# 35-CSI-GPM-CDSS_INTERFACE.net
KiCad netlist of a schematic drawn in Altium Designer
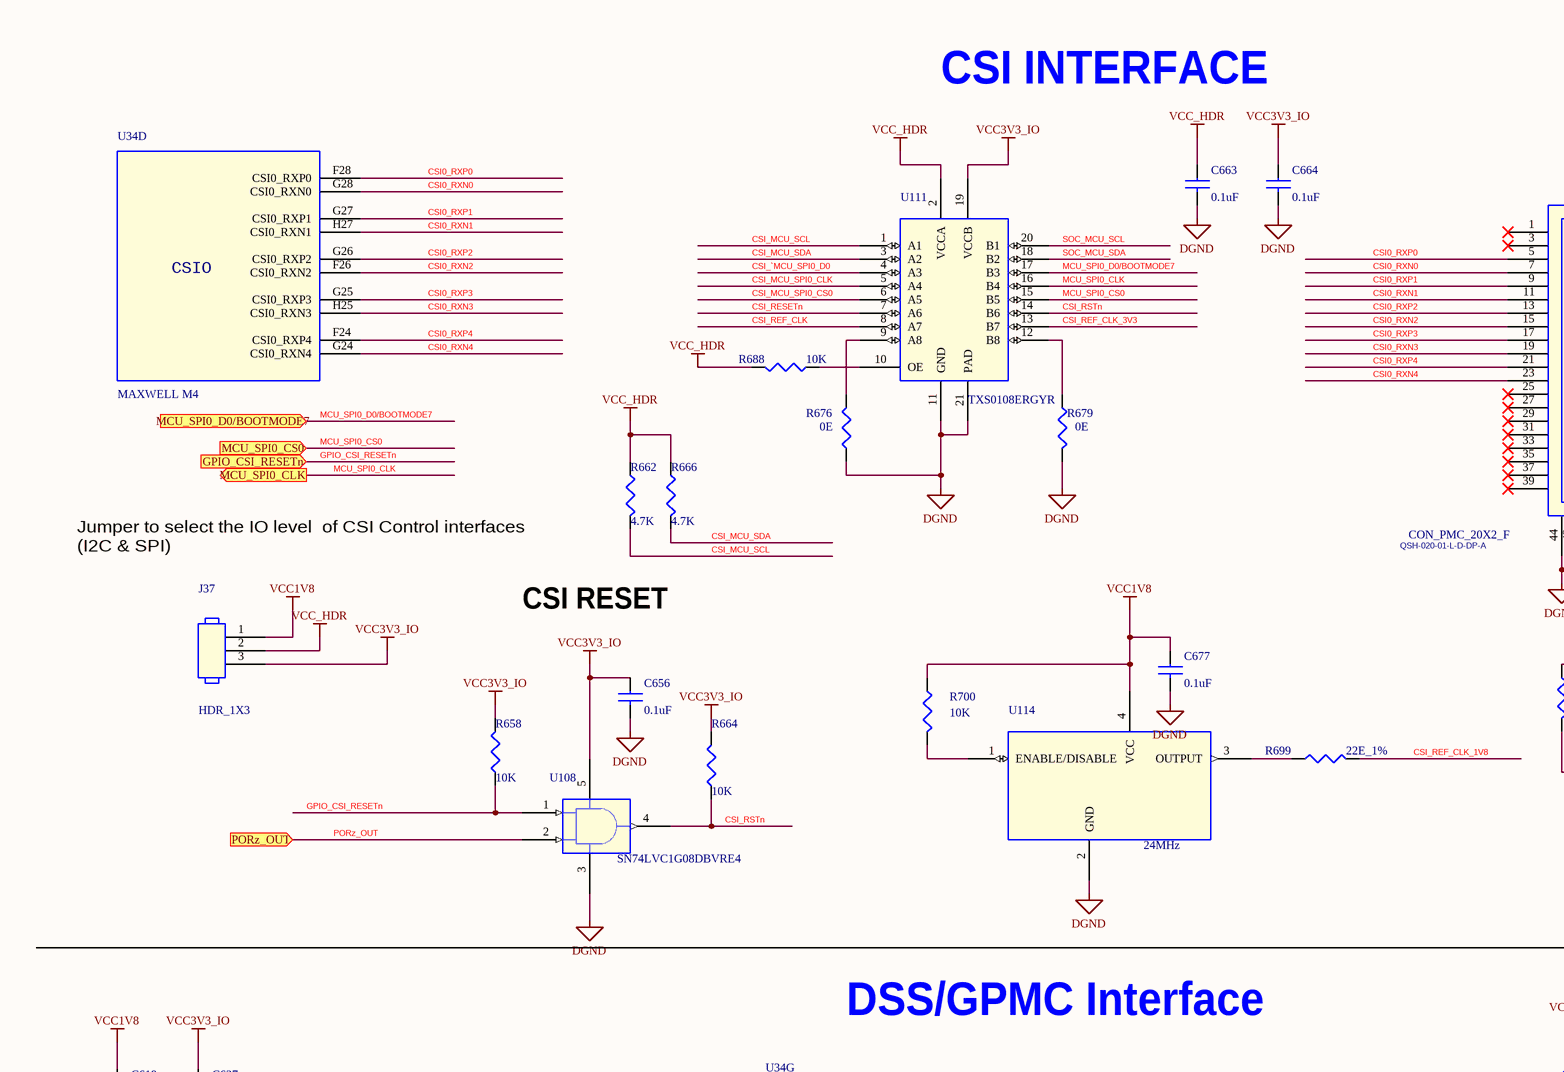
[diagram p0: 35-CSI-GPM-CDSS INTERFACE.SchDoc, top left]
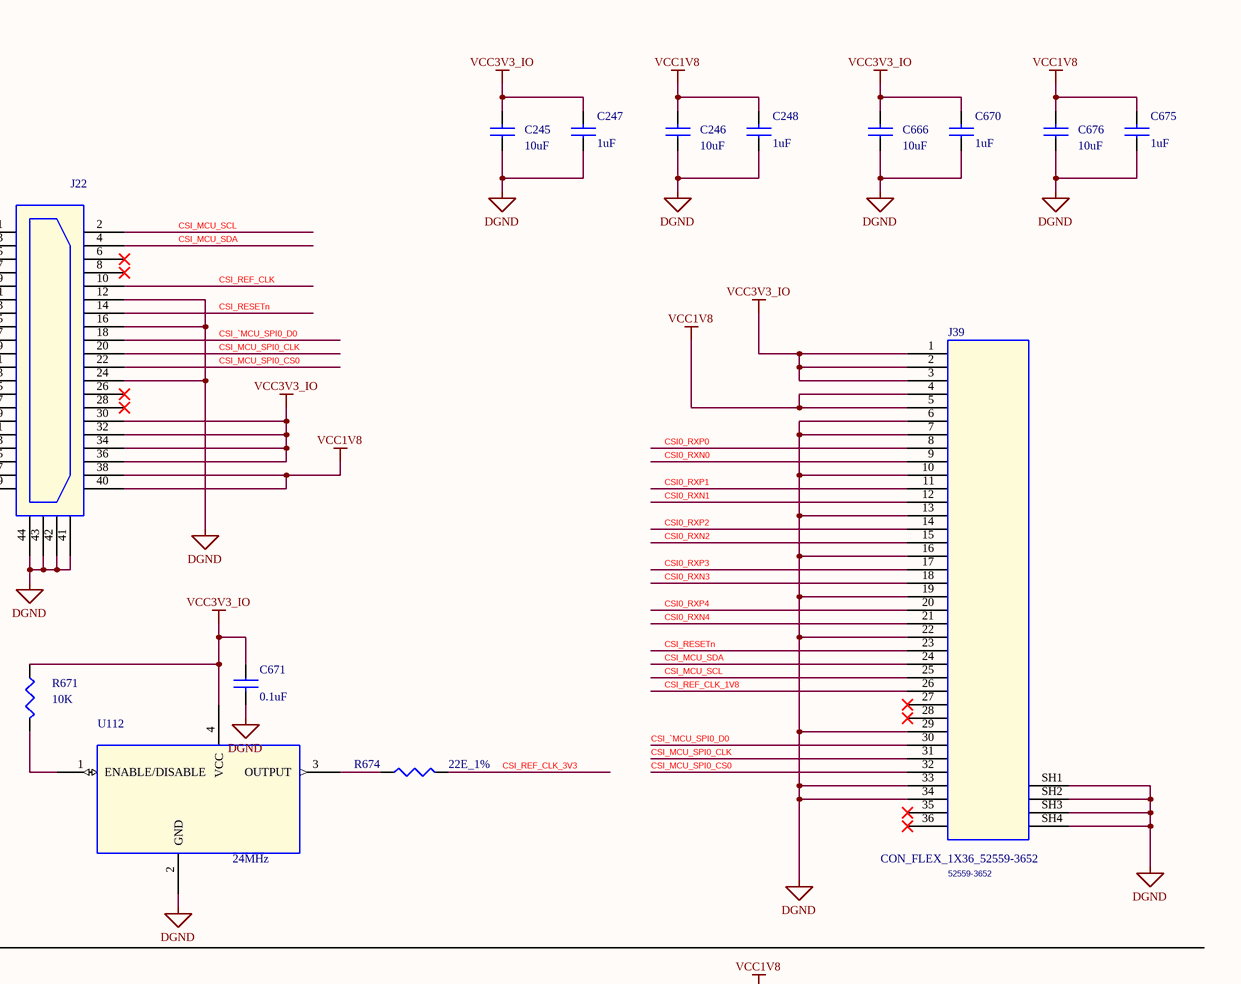
[diagram p1: 35-CSI-GPM-CDSS INTERFACE.SchDoc, top right]
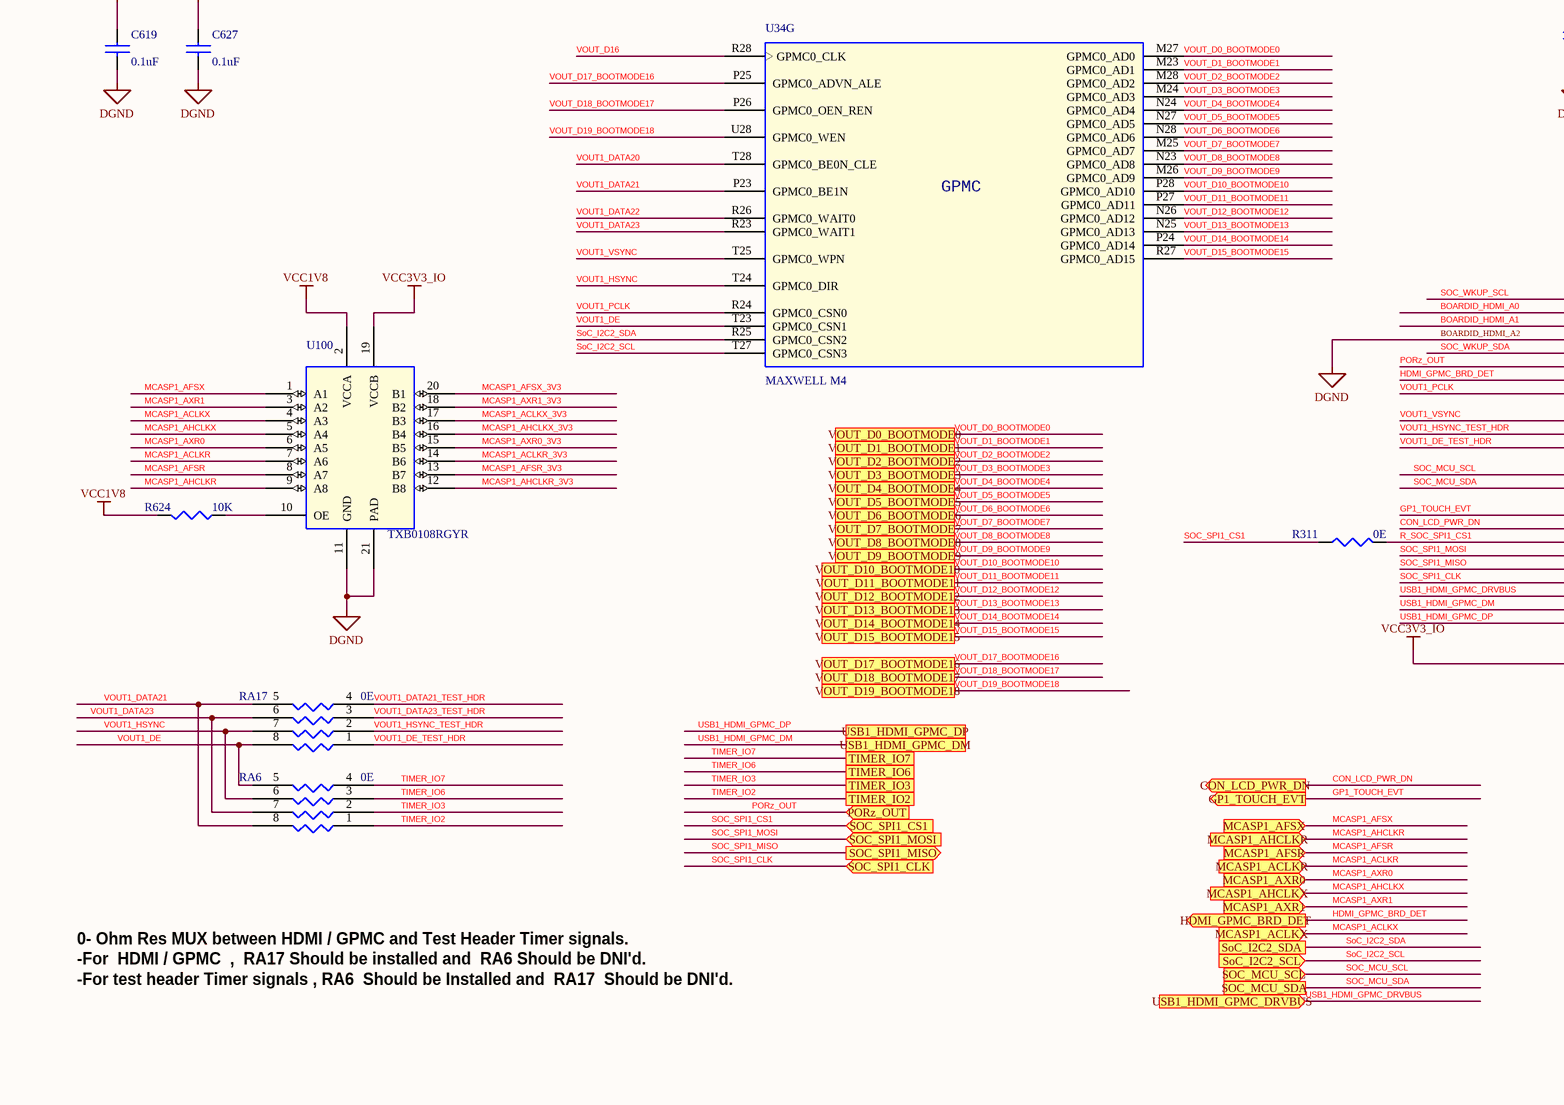
[diagram p2: 35-CSI-GPM-CDSS INTERFACE.SchDoc, bottom left]
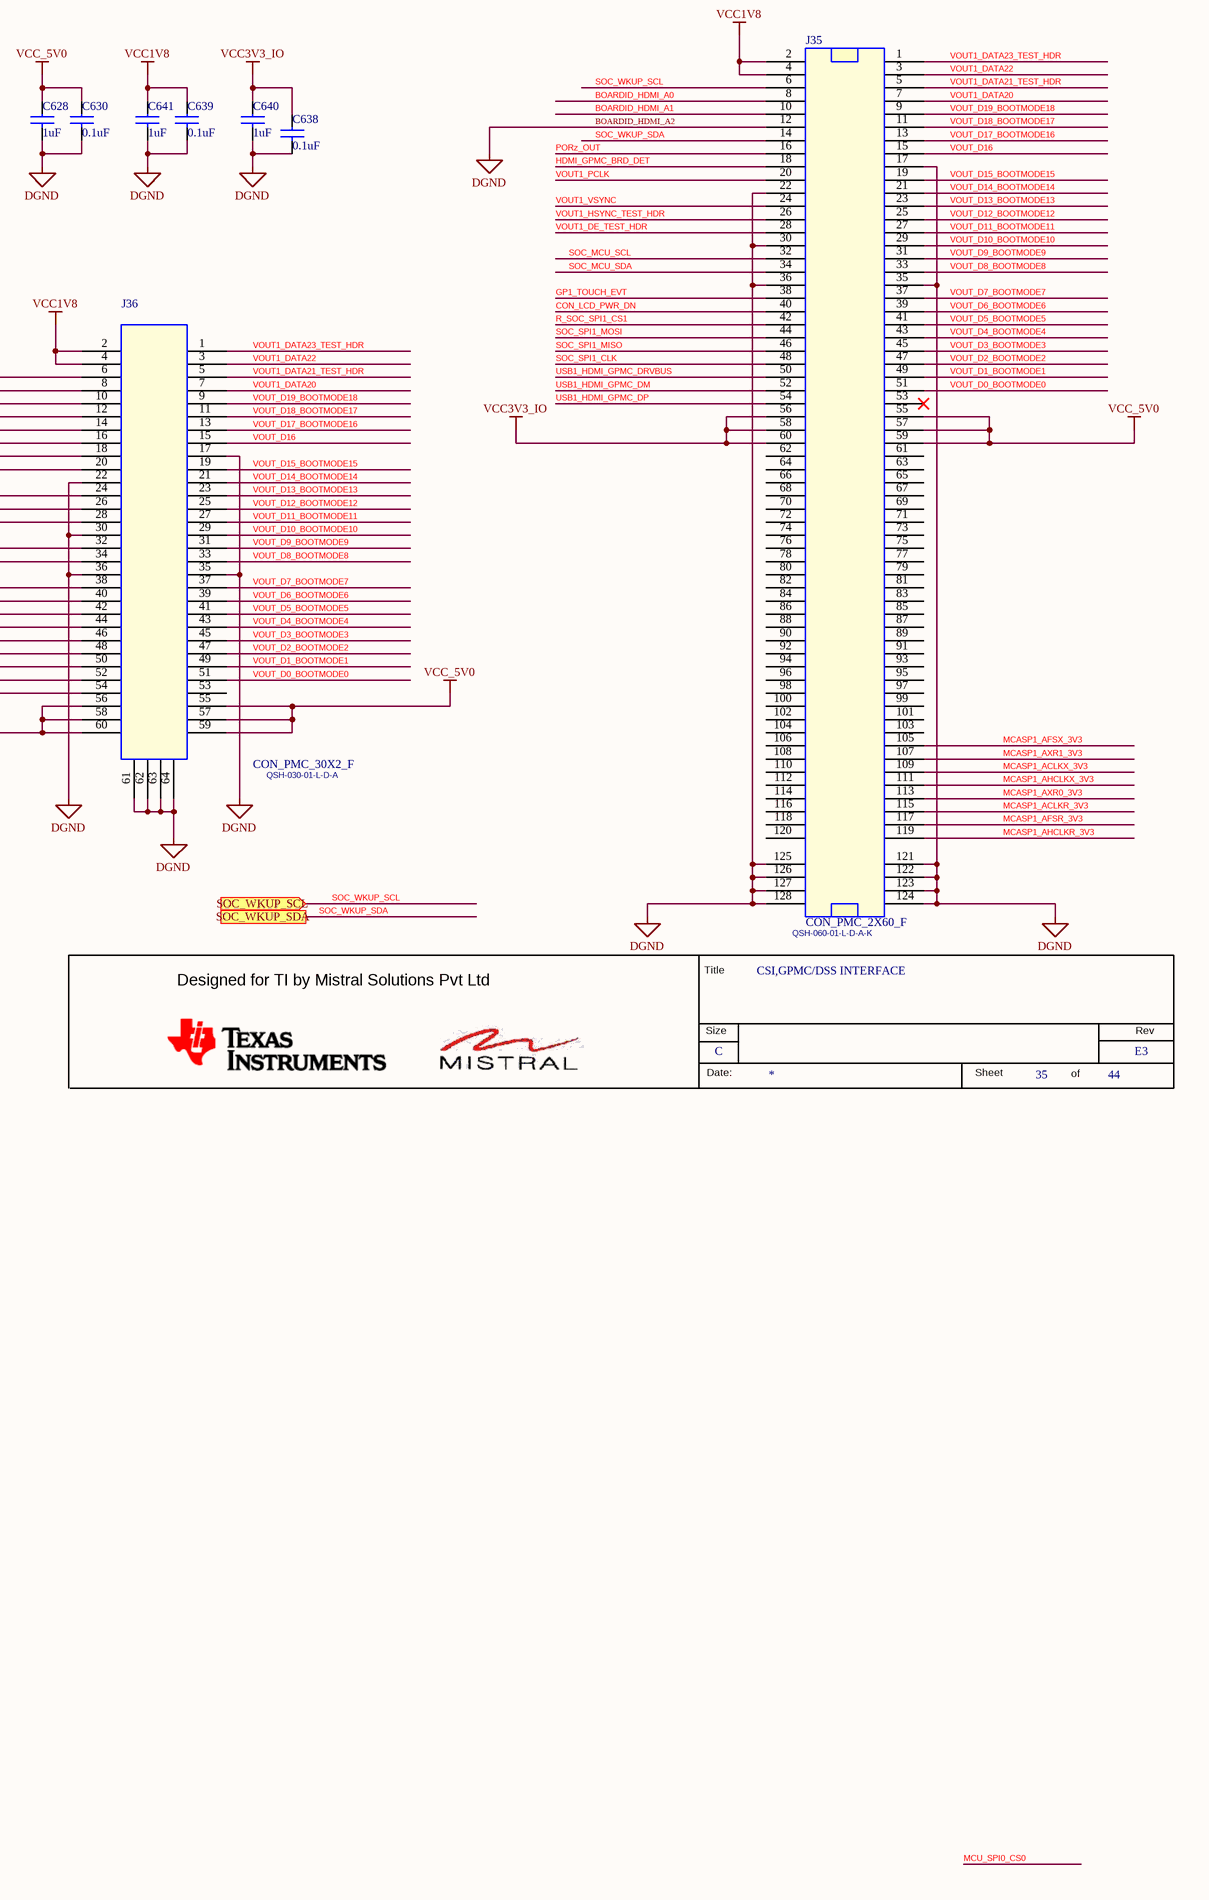
[diagram p3: 35-CSI-GPM-CDSS INTERFACE.SchDoc, bottom right]

(export (version "E")
  (design (tool "Eeschema 10.0.6"))
  (components
    (comp (ref "C245")
      (value "10uF")
      (footprint "CAP0603_1")
      (description "CAP CERAMIC 10uF 10V 10% X5R 0603")
      (fields
        (field (name "MISTRAL PART NO") "120010080001-R")
        (field (name "MFR_PART_NUMBER") "0603ZD106KAT2A")
      )
      (libsource (lib "*") (part "CAP_Dup5"))
    )
    (comp (ref "C246")
      (value "10uF")
      (footprint "CAP0603_1")
      (description "CAP CERAMIC 10uF 10V 10% X5R 0603")
      (fields (field (name "DISTRIBUTOR_PART_NUMBER") "478-10766-1-ND") (field (name "VOLTAGE") "10V"))
      (libsource (lib "*") (part "CAP_Dup5"))
    )
    (comp (ref "C247")
      (value "1uF")
      (footprint "CAP0402_0-75")
      (description "CAP CERAMIC 1uF 16V 20% X5R 0402")
      (fields (field (name "DISTRIBUTOR_PART_NUMBER") "587-5514-1-ND") (field (name "VOLTAGE") "16V"))
      (libsource (lib "*") (part "CAP_Dup5"))
    )
    (comp (ref "C248")
      (value "1uF")
      (footprint "CAP0402_0-75")
      (description "CAP CERAMIC 1uF 16V 20% X5R 0402")
      (fields
        (field (name "MISTRAL PART NO") "120018020006-R")
        (field (name "MFR_PART_NUMBER") "EMK105BJ105MV-F")
      )
      (libsource (lib "*") (part "CAP_Dup5"))
    )
    (comp (ref "C619")
      (value "0.1uF")
      (footprint "CAP0201_0-5")
      (description "CAP CERAMIC 0.1uF 16V 10% X5R 0201")
      (fields
        (field (name "MISTRAL PART NO") "120009030072-R")
        (field (name "MFR_PART_NUMBER") "GRM033R61C104KE84J")
      )
      (libsource (lib "*") (part "CAP_Dup5"))
    )
    (comp (ref "C627")
      (value "0.1uF")
      (footprint "CAP0201_0-5")
      (description "CAP CERAMIC 0.1uF 16V 10% X5R 0201")
      (fields
        (field (name "MISTRAL PART NO") "120009030072-R")
        (field (name "MFR_PART_NUMBER") "GRM033R61C104KE84J")
      )
      (libsource (lib "*") (part "CAP_Dup5"))
    )
    (comp (ref "C628")
      (value "1uF")
      (footprint "CAP0402_0-75")
      (description "CAP CERAMIC 1uF 16V 20% X5R 0402")
      (fields (field (name "DISTRIBUTOR_PART_NUMBER") "587-5514-1-ND") (field (name "VOLTAGE") "16V"))
      (libsource (lib "*") (part "CAP_Dup5"))
    )
    (comp (ref "C630")
      (value "0.1uF")
      (footprint "CAP0201_0-5")
      (description "CAP CERAMIC 0.1uF 16V 10% X5R 0201")
      (fields
        (field (name "MISTRAL PART NO") "120009030072-R")
        (field (name "MFR_PART_NUMBER") "GRM033R61C104KE84J")
      )
      (libsource (lib "*") (part "CAP_Dup5"))
    )
    (comp (ref "C638")
      (value "0.1uF")
      (footprint "CAP0201_0-5")
      (description "CAP CERAMIC 0.1uF 16V 10% X5R 0201")
      (fields (field (name "DISTRIBUTOR_PART_NUMBER") "490-16742-1-ND") (field (name "VOLTAGE") "16V"))
      (libsource (lib "*") (part "CAP_Dup5"))
    )
    (comp (ref "C639")
      (value "0.1uF")
      (footprint "CAP0201_0-5")
      (description "CAP CERAMIC 0.1uF 16V 10% X5R 0201")
      (fields (field (name "DISTRIBUTOR_PART_NUMBER") "490-16742-1-ND") (field (name "VOLTAGE") "16V"))
      (libsource (lib "*") (part "CAP_Dup5"))
    )
    (comp (ref "C640")
      (value "1uF")
      (footprint "CAP0402_0-75")
      (description "CAP CERAMIC 1uF 16V 20% X5R 0402")
      (fields (field (name "DISTRIBUTOR_PART_NUMBER") "587-5514-1-ND") (field (name "VOLTAGE") "16V"))
      (libsource (lib "*") (part "CAP_Dup5"))
    )
    (comp (ref "C641")
      (value "1uF")
      (footprint "CAP0402_0-75")
      (description "CAP CERAMIC 1uF 16V 20% X5R 0402")
      (fields
        (field (name "MISTRAL PART NO") "120018020006-R")
        (field (name "MFR_PART_NUMBER") "EMK105BJ105MV-F")
      )
      (libsource (lib "*") (part "CAP_Dup5"))
    )
    (comp (ref "C656")
      (value "0.1uF")
      (footprint "CAP0201_0-5")
      (description "CAP CERAMIC 0.1uF 16V 10% X5R 0201")
      (fields
        (field (name "MISTRAL PART NO") "120009030072-R")
        (field (name "MFR_PART_NUMBER") "GRM033R61C104KE84J")
      )
      (libsource (lib "*") (part "CAP_Dup5"))
    )
    (comp (ref "C663")
      (value "0.1uF")
      (footprint "CAP0201_0-5")
      (description "CAP CERAMIC 0.1uF 16V 10% X5R 0201")
      (fields
        (field (name "MISTRAL PART NO") "120009030072-R")
        (field (name "MFR_PART_NUMBER") "GRM033R61C104KE84J")
      )
      (libsource (lib "*") (part "CAP_Dup5"))
    )
    (comp (ref "C664")
      (value "0.1uF")
      (footprint "CAP0201_0-5")
      (description "CAP CERAMIC 0.1uF 16V 10% X5R 0201")
      (fields
        (field (name "MISTRAL PART NO") "120009030072-R")
        (field (name "MFR_PART_NUMBER") "GRM033R61C104KE84J")
      )
      (libsource (lib "*") (part "CAP_Dup5"))
    )
    (comp (ref "C666")
      (value "10uF")
      (footprint "CAP0603_1")
      (description "CAP CERAMIC 10uF 10V 10% X5R 0603")
      (fields
        (field (name "MISTRAL PART NO") "120010080001-R")
        (field (name "MFR_PART_NUMBER") "0603ZD106KAT2A")
      )
      (libsource (lib "*") (part "CAP_Dup5"))
    )
    (comp (ref "C670")
      (value "1uF")
      (footprint "CAP0402_0-75")
      (description "CAP CERAMIC 1uF 16V 20% X5R 0402")
      (fields (field (name "DISTRIBUTOR_PART_NUMBER") "587-5514-1-ND") (field (name "VOLTAGE") "16V"))
      (libsource (lib "*") (part "CAP_Dup5"))
    )
    (comp (ref "C671")
      (value "0.1uF")
      (footprint "CAP0201_0-5")
      (description "CAP CERAMIC 0.1uF 16V 10% X5R 0201")
      (fields
        (field (name "MISTRAL PART NO") "120009030072-R")
        (field (name "MFR_PART_NUMBER") "GRM033R61C104KE84J")
      )
      (libsource (lib "*") (part "CAP_Dup5"))
    )
    (comp (ref "C675")
      (value "1uF")
      (footprint "CAP0402_0-75")
      (description "CAP CERAMIC 1uF 16V 20% X5R 0402")
      (fields
        (field (name "MISTRAL PART NO") "120018020006-R")
        (field (name "MFR_PART_NUMBER") "EMK105BJ105MV-F")
      )
      (libsource (lib "*") (part "CAP_Dup5"))
    )
    (comp (ref "C676")
      (value "10uF")
      (footprint "CAP0603_1")
      (description "CAP CERAMIC 10uF 10V 10% X5R 0603")
      (fields (field (name "DISTRIBUTOR_PART_NUMBER") "478-10766-1-ND") (field (name "VOLTAGE") "10V"))
      (libsource (lib "*") (part "CAP_Dup5"))
    )
    (comp (ref "C677")
      (value "0.1uF")
      (footprint "CAP0201_0-5")
      (description "CAP CERAMIC 0.1uF 16V 10% X5R 0201")
      (fields
        (field (name "MISTRAL PART NO") "120009030072-R")
        (field (name "MFR_PART_NUMBER") "GRM033R61C104KE84J")
      )
      (libsource (lib "*") (part "CAP_Dup5"))
    )
    (comp (ref "J22")
      (value "CON_PMC_20X2_F")
      (footprint "CON_PMC20X2_QSH-D-DP_S_S_S")
      (description "CON PMC 20X2 0.50MM PITCH FEMALE ST SMD")
      (fields
        (field (name "DISTRIBUTOR_PART_NUMBER") "QSH-020-01-L-D-DP-A-ND")
        (field (name "VOLTAGE") "NA")
        (field (name "MFR_PART_NUMBER") "QSH-020-01-L-D-DP-A")
      )
      (libsource (lib "*") (part "CON_PMC_20X2_F"))
    )
    (comp (ref "J35")
      (value "CON_PMC_2X60_F")
      (footprint "CON_PMC60X2_HQCD-060_S_S_S_3-3")
      (description "CON PMC 2X60 0.50MM PITCH FEMALE ST SMD")
      (fields
        (field (name "MISTRAL PART NO") "150010060004-R")
        (field (name "MFR_PART_NUMBER") "QSH-060-01-L-D-A-K")
        (field (name "TOLERANCE") "NA")
      )
      (libsource (lib "*") (part "CON_PMC_60X2_HQCD"))
    )
    (comp (ref "J36")
      (value "CON_PMC_30X2_F")
      (footprint "CON_PMC30X2_QSH-030-01-L_S_S_S")
      (description "CON PMC 30X2 0.50MM PITCH FEMALE ST SMD")
      (fields
        (field (name "MFR_PART_NUMBER") "QSH-030-01-L-D-A")
        (field (name "MISTRAL PART NO") "150009030606")
      )
      (libsource (lib "*") (part "CON_PMC_30X2_F_Dup1"))
    )
    (comp (ref "J37")
      (value "HDR_1X3")
      (footprint "HDR_3X1_100_S_T")
      (description "HDR 1X3 2.54MM PITCH ST TH")
      (fields (field (name "DISTRIBUTOR_PART_NUMBER") "609-3471-ND") (field (name "VOLTAGE") "NA"))
      (libsource (lib "*") (part "HEADER_3X1"))
    )
    (comp (ref "J39")
      (value "CON_FLEX_1X36_52559-3652")
      (footprint "CON_FLEX1X36_52559-36_S_S_S_5-3")
      (description "CON FPC 1X36 0.50MM PITCH ST SMD")
      (fields
        (field (name "MISTRAL PART NO") "150017090006-R")
        (field (name "MFR_PART_NUMBER") "52559-3652")
        (field (name "TOLERANCE") "NA")
      )
      (libsource (lib "*") (part "CON_FLEX_36X1_52559-3652"))
    )
    (comp (ref "R311")
      (value "0E")
      (footprint "RES0402_0-5")
      (description "RES 0E 1/16W 0402")
      (fields
        (field (name "MISTRAL PART NO") "110010080019-P")
        (field (name "MFR_PART_NUMBER") "CRCW04020000Z0ED")
      )
      (libsource (lib "*") (part "RESISTOR_Dup5"))
    )
    (comp (ref "R624")
      (value "10K")
      (footprint "RES0402_0-5")
      (description "RES 10K 1/16W 5% 0402")
      (fields (field (name "DISTRIBUTOR_PART_NUMBER") "311-10KJRCT-ND") (field (name "VOLTAGE") "NA"))
      (libsource (lib "*") (part "RESISTOR_Dup5"))
    )
    (comp (ref "R658")
      (value "10K")
      (footprint "RES0402_0-5")
      (description "RES 10K 1/16W 5% 0402")
      (fields (field (name "DISTRIBUTOR_PART_NUMBER") "311-10KJRCT-ND") (field (name "VOLTAGE") "NA"))
      (libsource (lib "*") (part "RESISTOR_Dup5"))
    )
    (comp (ref "R662")
      (value "4.7K")
      (footprint "RES0402")
      (description "RES 4.7K 1/16W 5% 0402")
      (fields (field (name "DISTRIBUTOR_PART_NUMBER") "311-4.7KJRCT-ND") (field (name "VOLTAGE") "NA"))
      (libsource (lib "*") (part "RESISTOR_Dup3"))
    )
    (comp (ref "R664")
      (value "10K")
      (footprint "RES0402_0-5")
      (description "RES 10K 1/16W 5% 0402")
      (fields (field (name "DISTRIBUTOR_PART_NUMBER") "311-10KJRCT-ND") (field (name "VOLTAGE") "NA"))
      (libsource (lib "*") (part "RESISTOR_Dup5"))
    )
    (comp (ref "R666")
      (value "4.7K")
      (footprint "RES0402")
      (description "RES 4.7K 1/16W 5% 0402")
      (fields (field (name "DISTRIBUTOR_PART_NUMBER") "311-4.7KJRCT-ND") (field (name "VOLTAGE") "NA"))
      (libsource (lib "*") (part "RESISTOR_Dup3"))
    )
    (comp (ref "R671")
      (value "10K")
      (footprint "RES0402_0-5")
      (description "RES 10K 1/16W 5% 0402")
      (fields
        (field (name "MISTRAL PART NO") "110009030208-R")
        (field (name "MFR_PART_NUMBER") "RC0402JR-0710KL")
      )
      (libsource (lib "*") (part "RESISTOR_Dup5"))
    )
    (comp (ref "R674")
      (value "22E_1%")
      (footprint "RES0402")
      (description "RES 22E 1/16W 1% 0402")
      (fields
        (field (name "CUST_PART_NUMBER") "4700-80047E")
        (field (name "DISTRIBUTOR_PART_NUMBER") "311-22.0LRCT-ND")
      )
      (libsource (lib "*") (part "RESISTOR_Dup4"))
    )
    (comp (ref "R676")
      (value "0E")
      (footprint "RES0402_0-5")
      (description "RES 0E 1/16W 0402")
      (fields (field (name "DISTRIBUTOR_PART_NUMBER") "541-0.0JCT-ND") (field (name "VOLTAGE") "NA"))
      (libsource (lib "*") (part "RESISTOR_Dup5"))
    )
    (comp (ref "R679")
      (value "0E")
      (footprint "RES0402_0-5")
      (description "RES 0E 1/16W 0402")
      (fields
        (field (name "MISTRAL PART NO") "110010080019-P")
        (field (name "MFR_PART_NUMBER") "CRCW04020000Z0ED")
      )
      (libsource (lib "*") (part "RESISTOR_Dup5"))
    )
    (comp (ref "R688")
      (value "10K")
      (footprint "RES0402_0-5")
      (description "RES 10K 1/16W 5% 0402")
      (fields (field (name "DISTRIBUTOR_PART_NUMBER") "311-10KJRCT-ND") (field (name "VOLTAGE") "NA"))
      (libsource (lib "*") (part "RESISTOR_Dup5"))
    )
    (comp (ref "R699")
      (value "22E_1%")
      (footprint "RES0402")
      (description "RES 22E 1/16W 1% 0402")
      (fields
        (field (name "MISTRAL PART NO") "110009090004-P")
        (field (name "MFR_PART_NUMBER") "RC0402FR-0722RL")
      )
      (libsource (lib "*") (part "RESISTOR_Dup4"))
    )
    (comp (ref "R700")
      (value "10K")
      (footprint "RES0402_0-5")
      (description "RES 10K 1/16W 5% 0402")
      (fields
        (field (name "MISTRAL PART NO") "110009030208-R")
        (field (name "MFR_PART_NUMBER") "RC0402JR-0710KL")
      )
      (libsource (lib "*") (part "RESISTOR_Dup5"))
    )
    (comp (ref "RA6")
      (value "0E")
      (footprint "RESA_EXBN8V_0402-4_0-6")
      (description "RES ARRAY 0E 31mW 0402-4")
      (fields (field (name "TOLERANCE") "NA") (field (name "DISTRIBUTOR_PART_NUMBER") "Y10000CT-ND"))
      (libsource (lib "*") (part "RESARR_ISO4"))
    )
    (comp (ref "RA17")
      (value "0E")
      (footprint "RESA_EXBN8V_0402-4_0-6")
      (description "RES ARRAY 0E 31mW 0402-4")
      (fields (field (name "TOLERANCE") "NA") (field (name "MISTRAL PART NO") "110009030002-R"))
      (libsource (lib "*") (part "RESARR_ISO4"))
    )
    (comp (ref "U34")
      (value "MAXWELL M4")
      (footprint "BGA784_31-49_910X910_1-7")
      (description "IC MAXWELL MICRO CONTROLLER UNIT BGA784")
      (fields
        (field (name "MISTRAL PART NO") "141217100003")
        (field (name "MFR_PART_NUMBER") "MAXWELL M4_EVM")
      )
      (libsource (lib "*") (part "AM654X_BGA784"))
    )
    (comp (ref "U100")
      (value "TXB0108RGYR")
      (footprint "QFN20_19-68_185X145_1")
      (description "IC 8-BIT TRANSLATOR 15KV ESD VQFN20")
      (fields (field (name "MISTRAL PART NO") "141010050005-R") (field (name "TOLERANCE") "NA"))
      (libsource (lib "*") (part "TXB0108RGYR_VQFN20"))
    )
    (comp (ref "U108")
      (value "SN74LVC1G08DBVRE4")
      (footprint "SOT23-5")
      (description "IC SINGLE 2-INPUT POSITIVE AND GATE SOT23-5")
      (fields
        (field (name "MISTRAL PART NO") "141009060026-R")
        (field (name "DISTRIBUTOR_PART_NUMBER") "SN74LVC1G08DBVRE4-ND")
      )
      (libsource (lib "*") (part "SN74LVC1G08DBVRE4_SOT23-5"))
    )
    (comp (ref "U111")
      (value "TXS0108ERGYR")
      (footprint "QFN20_19-68_185X145_1")
      (description "IC TRANSLATOR BIDIRECTIONAL VOLTAGE-LEVEL 8BIT QFN20")
      (fields (field (name "MISTRAL PART NO") "141011040019-R") (field (name "TOLERANCE") "NA"))
      (libsource (lib "*") (part "TXS0108ERGYR_QFN20"))
    )
    (comp (ref "U112")
      (value "24MHz")
      (footprint "OSC4_KC2520B_100X80_SMD")
      (description "OSC 24MHz 1.8V SMD")
      (fields
        (field (name "MISTRAL PART NO") "130015030022-R")
        (field (name "MFR_PART_NUMBER") "KC2520B24.0000C1GE00")
      )
      (libsource (lib "*") (part "OSC_KC2520B"))
    )
    (comp (ref "U114")
      (value "24MHz")
      (footprint "OSC4_KC2520B_100X80_SMD")
      (description "OSC 24MHz 1.8V SMD")
      (fields
        (field (name "MISTRAL PART NO") "130015030022-R")
        (field (name "MFR_PART_NUMBER") "KC2520B24.0000C1GE00")
      )
      (libsource (lib "*") (part "OSC_KC2520B"))
    )
  )
  (nets
    (net (code "1") (name "/BOARDID_HDMI_A0") (class "Default")
      (node (ref "J35") (pin "8") (pinfunction "8_8") (pintype "passive"))
      (node (ref "J36") (pin "8") (pinfunction "8_8") (pintype "passive"))
    )
    (net (code "2") (name "/BOARDID_HDMI_A1") (class "Default")
      (node (ref "J35") (pin "10") (pinfunction "10_10") (pintype "passive"))
      (node (ref "J36") (pin "10") (pinfunction "10_10") (pintype "passive"))
    )
    (net (code "3") (name "/CON_LCD_PWR_DN") (class "Default")
      (node (ref "J35") (pin "40") (pinfunction "40_40") (pintype "passive"))
      (node (ref "J36") (pin "40") (pinfunction "40_40") (pintype "passive"))
    )
    (net (code "4") (name "/CSI0_RXN0") (class "Default")
      (node (ref "J22") (pin "7") (pinfunction "7_7") (pintype "passive"))
      (node (ref "J39") (pin "9") (pinfunction "9_9") (pintype "passive"))
      (node (ref "U34") (pin "G28") (pinfunction "CSI0_RXN0_G28") (pintype "passive"))
    )
    (net (code "5") (name "/CSI0_RXN1") (class "Default")
      (node (ref "J22") (pin "11") (pinfunction "11_11") (pintype "passive"))
      (node (ref "J39") (pin "12") (pinfunction "12_12") (pintype "passive"))
      (node (ref "U34") (pin "H27") (pinfunction "CSI0_RXN1_H27") (pintype "passive"))
    )
    (net (code "6") (name "/CSI0_RXN2") (class "Default")
      (node (ref "J22") (pin "15") (pinfunction "15_15") (pintype "passive"))
      (node (ref "J39") (pin "15") (pinfunction "15_15") (pintype "passive"))
      (node (ref "U34") (pin "F26") (pinfunction "CSI0_RXN2_F26") (pintype "passive"))
    )
    (net (code "7") (name "/CSI0_RXN3") (class "Default")
      (node (ref "J22") (pin "19") (pinfunction "19_19") (pintype "passive"))
      (node (ref "J39") (pin "18") (pinfunction "18_18") (pintype "passive"))
      (node (ref "U34") (pin "H25") (pinfunction "CSI0_RXN3_H25") (pintype "passive"))
    )
    (net (code "8") (name "/CSI0_RXN4") (class "Default")
      (node (ref "J22") (pin "23") (pinfunction "23_23") (pintype "passive"))
      (node (ref "J39") (pin "21") (pinfunction "21_21") (pintype "passive"))
      (node (ref "U34") (pin "G24") (pinfunction "CSI0_RXN4_G24") (pintype "passive"))
    )
    (net (code "9") (name "/CSI0_RXP0") (class "Default")
      (node (ref "J22") (pin "5") (pinfunction "5_5") (pintype "passive"))
      (node (ref "J39") (pin "8") (pinfunction "8_8") (pintype "passive"))
      (node (ref "U34") (pin "F28") (pinfunction "CSI0_RXP0_F28") (pintype "passive"))
    )
    (net (code "10") (name "/CSI0_RXP1") (class "Default")
      (node (ref "J22") (pin "9") (pinfunction "9_9") (pintype "passive"))
      (node (ref "J39") (pin "11") (pinfunction "11_11") (pintype "passive"))
      (node (ref "U34") (pin "G27") (pinfunction "CSI0_RXP1_G27") (pintype "passive"))
    )
    (net (code "11") (name "/CSI0_RXP2") (class "Default")
      (node (ref "J22") (pin "13") (pinfunction "13_13") (pintype "passive"))
      (node (ref "J39") (pin "14") (pinfunction "14_14") (pintype "passive"))
      (node (ref "U34") (pin "G26") (pinfunction "CSI0_RXP2_G26") (pintype "passive"))
    )
    (net (code "12") (name "/CSI0_RXP3") (class "Default")
      (node (ref "J22") (pin "17") (pinfunction "17_17") (pintype "passive"))
      (node (ref "J39") (pin "17") (pinfunction "17_17") (pintype "passive"))
      (node (ref "U34") (pin "G25") (pinfunction "CSI0_RXP3_G25") (pintype "passive"))
    )
    (net (code "13") (name "/CSI0_RXP4") (class "Default")
      (node (ref "J22") (pin "21") (pinfunction "21_21") (pintype "passive"))
      (node (ref "J39") (pin "20") (pinfunction "20_20") (pintype "passive"))
      (node (ref "U34") (pin "F24") (pinfunction "CSI0_RXP4_F24") (pintype "passive"))
    )
    (net (code "14") (name "/CSI_MCU_SCL") (class "Default")
      (node (ref "J22") (pin "2") (pinfunction "2_2") (pintype "passive"))
      (node (ref "J39") (pin "25") (pinfunction "25_25") (pintype "passive"))
      (node (ref "R662") (pin "2") (pinfunction "2_2") (pintype "passive"))
      (node (ref "U111") (pin "1") (pinfunction "A1_1") (pintype "bidirectional"))
    )
    (net (code "15") (name "/CSI_MCU_SDA") (class "Default")
      (node (ref "J22") (pin "4") (pinfunction "4_4") (pintype "passive"))
      (node (ref "J39") (pin "24") (pinfunction "24_24") (pintype "passive"))
      (node (ref "R666") (pin "2") (pinfunction "2_2") (pintype "passive"))
      (node (ref "U111") (pin "3") (pinfunction "A2_3") (pintype "bidirectional"))
    )
    (net (code "16") (name "/CSI_MCU_SPI0_CLK") (class "Default")
      (node (ref "J22") (pin "20") (pinfunction "20_20") (pintype "passive"))
      (node (ref "J39") (pin "31") (pinfunction "31_31") (pintype "passive"))
      (node (ref "U111") (pin "5") (pinfunction "A4_5") (pintype "bidirectional"))
    )
    (net (code "17") (name "/CSI_MCU_SPI0_CS0") (class "Default")
      (node (ref "J22") (pin "22") (pinfunction "22_22") (pintype "passive"))
      (node (ref "J39") (pin "32") (pinfunction "32_32") (pintype "passive"))
      (node (ref "U111") (pin "6") (pinfunction "A5_6") (pintype "bidirectional"))
    )
    (net (code "18") (name "/CSI_REF_CLK") (class "Default")
      (node (ref "J22") (pin "10") (pinfunction "10_10") (pintype "passive"))
      (node (ref "U111") (pin "8") (pinfunction "A7_8") (pintype "bidirectional"))
    )
    (net (code "19") (name "/CSI_REF_CLK_1V8") (class "Default")
      (node (ref "J39") (pin "26") (pinfunction "26_26") (pintype "passive"))
      (node (ref "R699") (pin "2") (pinfunction "2_2") (pintype "passive"))
    )
    (net (code "20") (name "/CSI_REF_CLK_3V3") (class "Default")
      (node (ref "R674") (pin "2") (pinfunction "2_2") (pintype "passive"))
      (node (ref "U111") (pin "13") (pinfunction "B7_13") (pintype "bidirectional"))
    )
    (net (code "21") (name "/CSI_RESETn") (class "Default")
      (node (ref "J22") (pin "14") (pinfunction "14_14") (pintype "passive"))
      (node (ref "J39") (pin "23") (pinfunction "23_23") (pintype "passive"))
      (node (ref "U111") (pin "7") (pinfunction "A6_7") (pintype "bidirectional"))
    )
    (net (code "22") (name "/CSI_RSTn") (class "Default")
      (node (ref "R664") (pin "1") (pinfunction "1_1") (pintype "passive"))
      (node (ref "U108") (pin "4") (pinfunction "Y_4") (pintype "output"))
      (node (ref "U111") (pin "14") (pinfunction "B6_14") (pintype "bidirectional"))
    )
    (net (code "23") (name "/CSI_`MCU_SPI0_D0") (class "Default")
      (node (ref "J22") (pin "18") (pinfunction "18_18") (pintype "passive"))
      (node (ref "J39") (pin "30") (pinfunction "30_30") (pintype "passive"))
      (node (ref "U111") (pin "4") (pinfunction "A3_4") (pintype "bidirectional"))
    )
    (net (code "24") (name "/GP1_TOUCH_EVT") (class "Default")
      (node (ref "J35") (pin "38") (pinfunction "38_38") (pintype "passive"))
      (node (ref "J36") (pin "38") (pinfunction "38_38") (pintype "passive"))
    )
    (net (code "25") (name "/GPIO_CSI_RESETn") (class "Default")
      (node (ref "R658") (pin "1") (pinfunction "1_1") (pintype "passive"))
      (node (ref "U108") (pin "1") (pinfunction "A_1") (pintype "input"))
    )
    (net (code "26") (name "/HDMI_GPMC_BRD_DET") (class "Default")
      (node (ref "J35") (pin "18") (pinfunction "18_18") (pintype "passive"))
      (node (ref "J36") (pin "18") (pinfunction "18_18") (pintype "passive"))
    )
    (net (code "27") (name "/MCASP1_ACLKR") (class "Default")
      (node (ref "U100") (pin "7") (pinfunction "A6_7") (pintype "bidirectional"))
    )
    (net (code "28") (name "/MCASP1_ACLKR_3V3") (class "Default")
      (node (ref "J35") (pin "115") (pinfunction "115_115") (pintype "passive"))
      (node (ref "U100") (pin "14") (pinfunction "B6_14") (pintype "bidirectional"))
    )
    (net (code "29") (name "/MCASP1_ACLKX") (class "Default")
      (node (ref "U100") (pin "4") (pinfunction "A3_4") (pintype "bidirectional"))
    )
    (net (code "30") (name "/MCASP1_ACLKX_3V3") (class "Default")
      (node (ref "J35") (pin "109") (pinfunction "109_109") (pintype "passive"))
      (node (ref "U100") (pin "17") (pinfunction "B3_17") (pintype "bidirectional"))
    )
    (net (code "31") (name "/MCASP1_AFSR") (class "Default")
      (node (ref "U100") (pin "8") (pinfunction "A7_8") (pintype "bidirectional"))
    )
    (net (code "32") (name "/MCASP1_AFSR_3V3") (class "Default")
      (node (ref "J35") (pin "117") (pinfunction "117_117") (pintype "passive"))
      (node (ref "U100") (pin "13") (pinfunction "B7_13") (pintype "bidirectional"))
    )
    (net (code "33") (name "/MCASP1_AFSX") (class "Default")
      (node (ref "U100") (pin "1") (pinfunction "A1_1") (pintype "bidirectional"))
    )
    (net (code "34") (name "/MCASP1_AFSX_3V3") (class "Default")
      (node (ref "J35") (pin "105") (pinfunction "105_105") (pintype "passive"))
      (node (ref "U100") (pin "20") (pinfunction "B1_20") (pintype "bidirectional"))
    )
    (net (code "35") (name "/MCASP1_AHCLKR") (class "Default")
      (node (ref "U100") (pin "9") (pinfunction "A8_9") (pintype "bidirectional"))
    )
    (net (code "36") (name "/MCASP1_AHCLKR_3V3") (class "Default")
      (node (ref "J35") (pin "119") (pinfunction "119_119") (pintype "passive"))
      (node (ref "U100") (pin "12") (pinfunction "B8_12") (pintype "bidirectional"))
    )
    (net (code "37") (name "/MCASP1_AHCLKX") (class "Default")
      (node (ref "U100") (pin "5") (pinfunction "A4_5") (pintype "bidirectional"))
    )
    (net (code "38") (name "/MCASP1_AHCLKX_3V3") (class "Default")
      (node (ref "J35") (pin "111") (pinfunction "111_111") (pintype "passive"))
      (node (ref "U100") (pin "16") (pinfunction "B4_16") (pintype "bidirectional"))
    )
    (net (code "39") (name "/MCASP1_AXR0") (class "Default")
      (node (ref "U100") (pin "6") (pinfunction "A5_6") (pintype "bidirectional"))
    )
    (net (code "40") (name "/MCASP1_AXR0_3V3") (class "Default")
      (node (ref "J35") (pin "113") (pinfunction "113_113") (pintype "passive"))
      (node (ref "U100") (pin "15") (pinfunction "B5_15") (pintype "bidirectional"))
    )
    (net (code "41") (name "/MCASP1_AXR1") (class "Default")
      (node (ref "U100") (pin "3") (pinfunction "A2_3") (pintype "bidirectional"))
    )
    (net (code "42") (name "/MCASP1_AXR1_3V3") (class "Default")
      (node (ref "J35") (pin "107") (pinfunction "107_107") (pintype "passive"))
      (node (ref "U100") (pin "18") (pinfunction "B2_18") (pintype "bidirectional"))
    )
    (net (code "43") (name "/MCU_SPI0_CLK") (class "Default")
      (node (ref "U111") (pin "16") (pinfunction "B4_16") (pintype "bidirectional"))
    )
    (net (code "44") (name "/MCU_SPI0_CS0") (class "Default")
      (node (ref "U111") (pin "15") (pinfunction "B5_15") (pintype "bidirectional"))
    )
    (net (code "45") (name "/MCU_SPI0_D0{slash}BOOTMODE7") (class "Default")
      (node (ref "U111") (pin "17") (pinfunction "B3_17") (pintype "bidirectional"))
    )
    (net (code "46") (name "/PORz_OUT") (class "Default")
      (node (ref "J35") (pin "16") (pinfunction "16_16") (pintype "passive"))
      (node (ref "J36") (pin "16") (pinfunction "16_16") (pintype "passive"))
      (node (ref "U108") (pin "2") (pinfunction "B_2") (pintype "input"))
    )
    (net (code "47") (name "/R_SOC_SPI1_CS1") (class "Default")
      (node (ref "J35") (pin "42") (pinfunction "42_42") (pintype "passive"))
      (node (ref "J36") (pin "42") (pinfunction "42_42") (pintype "passive"))
      (node (ref "R311") (pin "2") (pinfunction "2_2") (pintype "passive"))
    )
    (net (code "48") (name "/SOC_MCU_SCL") (class "Default")
      (node (ref "J35") (pin "32") (pinfunction "32_32") (pintype "passive"))
      (node (ref "J36") (pin "32") (pinfunction "32_32") (pintype "passive"))
      (node (ref "U111") (pin "20") (pinfunction "B1_20") (pintype "bidirectional"))
    )
    (net (code "49") (name "/SOC_MCU_SDA") (class "Default")
      (node (ref "J35") (pin "34") (pinfunction "34_34") (pintype "passive"))
      (node (ref "J36") (pin "34") (pinfunction "34_34") (pintype "passive"))
      (node (ref "U111") (pin "18") (pinfunction "B2_18") (pintype "bidirectional"))
    )
    (net (code "50") (name "/SOC_SPI1_CLK") (class "Default")
      (node (ref "J35") (pin "48") (pinfunction "48_48") (pintype "passive"))
      (node (ref "J36") (pin "48") (pinfunction "48_48") (pintype "passive"))
    )
    (net (code "51") (name "/SOC_SPI1_CS1") (class "Default")
      (node (ref "R311") (pin "1") (pinfunction "1_1") (pintype "passive"))
    )
    (net (code "52") (name "/SOC_SPI1_MISO") (class "Default")
      (node (ref "J35") (pin "46") (pinfunction "46_46") (pintype "passive"))
      (node (ref "J36") (pin "46") (pinfunction "46_46") (pintype "passive"))
    )
    (net (code "53") (name "/SOC_SPI1_MOSI") (class "Default")
      (node (ref "J35") (pin "44") (pinfunction "44_44") (pintype "passive"))
      (node (ref "J36") (pin "44") (pinfunction "44_44") (pintype "passive"))
    )
    (net (code "54") (name "/SOC_WKUP_SCL") (class "Default")
      (node (ref "J35") (pin "6") (pinfunction "6_6") (pintype "passive"))
      (node (ref "J36") (pin "6") (pinfunction "6_6") (pintype "passive"))
    )
    (net (code "55") (name "/SOC_WKUP_SDA") (class "Default")
      (node (ref "J35") (pin "14") (pinfunction "14_14") (pintype "passive"))
      (node (ref "J36") (pin "14") (pinfunction "14_14") (pintype "passive"))
    )
    (net (code "56") (name "/SoC_I2C2_SCL") (class "Default")
      (node (ref "U34") (pin "T27") (pinfunction "GPMC0_CSN3_T27") (pintype "passive"))
    )
    (net (code "57") (name "/SoC_I2C2_SDA") (class "Default")
      (node (ref "U34") (pin "R25") (pinfunction "GPMC0_CSN2_R25") (pintype "passive"))
    )
    (net (code "58") (name "/TIMER_IO2") (class "Default")
      (node (ref "RA6") (pin "1") (pinfunction "1_1") (pintype "passive"))
    )
    (net (code "59") (name "/TIMER_IO3") (class "Default")
      (node (ref "RA6") (pin "2") (pinfunction "2_2") (pintype "passive"))
    )
    (net (code "60") (name "/TIMER_IO6") (class "Default")
      (node (ref "RA6") (pin "3") (pinfunction "3_3") (pintype "passive"))
    )
    (net (code "61") (name "/TIMER_IO7") (class "Default")
      (node (ref "RA6") (pin "4") (pinfunction "4_4") (pintype "passive"))
    )
    (net (code "62") (name "/USB1_HDMI_GPMC_DM") (class "Default")
      (node (ref "J35") (pin "52") (pinfunction "52_52") (pintype "passive"))
      (node (ref "J36") (pin "52") (pinfunction "52_52") (pintype "passive"))
    )
    (net (code "63") (name "/USB1_HDMI_GPMC_DP") (class "Default")
      (node (ref "J35") (pin "54") (pinfunction "54_54") (pintype "passive"))
      (node (ref "J36") (pin "54") (pinfunction "54_54") (pintype "passive"))
    )
    (net (code "64") (name "/USB1_HDMI_GPMC_DRVBUS") (class "Default")
      (node (ref "J35") (pin "50") (pinfunction "50_50") (pintype "passive"))
      (node (ref "J36") (pin "50") (pinfunction "50_50") (pintype "passive"))
    )
    (net (code "65") (name "/VOUT1_DATA20") (class "Default")
      (node (ref "J35") (pin "7") (pinfunction "7_7") (pintype "passive"))
      (node (ref "J36") (pin "7") (pinfunction "7_7") (pintype "passive"))
      (node (ref "U34") (pin "T28") (pinfunction "GPMC0_BE0N_CLE_T28") (pintype "passive"))
    )
    (net (code "66") (name "/VOUT1_DATA21") (class "Default")
      (node (ref "RA17") (pin "5") (pinfunction "5_5") (pintype "passive"))
      (node (ref "RA6") (pin "8") (pinfunction "8_8") (pintype "passive"))
      (node (ref "U34") (pin "P23") (pinfunction "GPMC0_BE1N_P23") (pintype "passive"))
    )
    (net (code "67") (name "/VOUT1_DATA21_TEST_HDR") (class "Default")
      (node (ref "J35") (pin "5") (pinfunction "5_5") (pintype "passive"))
      (node (ref "J36") (pin "5") (pinfunction "5_5") (pintype "passive"))
      (node (ref "RA17") (pin "4") (pinfunction "4_4") (pintype "passive"))
    )
    (net (code "68") (name "/VOUT1_DATA22") (class "Default")
      (node (ref "J35") (pin "3") (pinfunction "3_3") (pintype "passive"))
      (node (ref "J36") (pin "3") (pinfunction "3_3") (pintype "passive"))
      (node (ref "U34") (pin "R26") (pinfunction "GPMC0_WAIT0_R26") (pintype "passive"))
    )
    (net (code "69") (name "/VOUT1_DATA23") (class "Default")
      (node (ref "RA17") (pin "6") (pinfunction "6_6") (pintype "passive"))
      (node (ref "RA6") (pin "7") (pinfunction "7_7") (pintype "passive"))
      (node (ref "U34") (pin "R23") (pinfunction "GPMC0_WAIT1_R23") (pintype "passive"))
    )
    (net (code "70") (name "/VOUT1_DATA23_TEST_HDR") (class "Default")
      (node (ref "J35") (pin "1") (pinfunction "1_1") (pintype "passive"))
      (node (ref "J36") (pin "1") (pinfunction "1_1") (pintype "passive"))
      (node (ref "RA17") (pin "3") (pinfunction "3_3") (pintype "passive"))
    )
    (net (code "71") (name "/VOUT1_DE") (class "Default")
      (node (ref "RA17") (pin "8") (pinfunction "8_8") (pintype "passive"))
      (node (ref "RA6") (pin "5") (pinfunction "5_5") (pintype "passive"))
      (node (ref "U34") (pin "T23") (pinfunction "GPMC0_CSN1_T23") (pintype "passive"))
    )
    (net (code "72") (name "/VOUT1_DE_TEST_HDR") (class "Default")
      (node (ref "J35") (pin "28") (pinfunction "28_28") (pintype "passive"))
      (node (ref "J36") (pin "28") (pinfunction "28_28") (pintype "passive"))
      (node (ref "RA17") (pin "1") (pinfunction "1_1") (pintype "passive"))
    )
    (net (code "73") (name "/VOUT1_HSYNC") (class "Default")
      (node (ref "RA17") (pin "7") (pinfunction "7_7") (pintype "passive"))
      (node (ref "RA6") (pin "6") (pinfunction "6_6") (pintype "passive"))
      (node (ref "U34") (pin "T24") (pinfunction "GPMC0_DIR_T24") (pintype "passive"))
    )
    (net (code "74") (name "/VOUT1_HSYNC_TEST_HDR") (class "Default")
      (node (ref "J35") (pin "26") (pinfunction "26_26") (pintype "passive"))
      (node (ref "J36") (pin "26") (pinfunction "26_26") (pintype "passive"))
      (node (ref "RA17") (pin "2") (pinfunction "2_2") (pintype "passive"))
    )
    (net (code "75") (name "/VOUT1_PCLK") (class "Default")
      (node (ref "J35") (pin "20") (pinfunction "20_20") (pintype "passive"))
      (node (ref "J36") (pin "20") (pinfunction "20_20") (pintype "passive"))
      (node (ref "U34") (pin "R24") (pinfunction "GPMC0_CSN0_R24") (pintype "passive"))
    )
    (net (code "76") (name "/VOUT1_VSYNC") (class "Default")
      (node (ref "J35") (pin "24") (pinfunction "24_24") (pintype "passive"))
      (node (ref "J36") (pin "24") (pinfunction "24_24") (pintype "passive"))
      (node (ref "U34") (pin "T25") (pinfunction "GPMC0_WPN_T25") (pintype "passive"))
    )
    (net (code "77") (name "/VOUT_D0_BOOTMODE0") (class "Default")
      (node (ref "J35") (pin "51") (pinfunction "51_51") (pintype "passive"))
      (node (ref "J36") (pin "51") (pinfunction "51_51") (pintype "passive"))
      (node (ref "U34") (pin "M27") (pinfunction "GPMC0_AD0_M27") (pintype "passive"))
    )
    (net (code "78") (name "/VOUT_D1_BOOTMODE1") (class "Default")
      (node (ref "J35") (pin "49") (pinfunction "49_49") (pintype "passive"))
      (node (ref "J36") (pin "49") (pinfunction "49_49") (pintype "passive"))
      (node (ref "U34") (pin "M23") (pinfunction "GPMC0_AD1_M23") (pintype "passive"))
    )
    (net (code "79") (name "/VOUT_D2_BOOTMODE2") (class "Default")
      (node (ref "J35") (pin "47") (pinfunction "47_47") (pintype "passive"))
      (node (ref "J36") (pin "47") (pinfunction "47_47") (pintype "passive"))
      (node (ref "U34") (pin "M28") (pinfunction "GPMC0_AD2_M28") (pintype "passive"))
    )
    (net (code "80") (name "/VOUT_D3_BOOTMODE3") (class "Default")
      (node (ref "J35") (pin "45") (pinfunction "45_45") (pintype "passive"))
      (node (ref "J36") (pin "45") (pinfunction "45_45") (pintype "passive"))
      (node (ref "U34") (pin "M24") (pinfunction "GPMC0_AD3_M24") (pintype "passive"))
    )
    (net (code "81") (name "/VOUT_D4_BOOTMODE4") (class "Default")
      (node (ref "J35") (pin "43") (pinfunction "43_43") (pintype "passive"))
      (node (ref "J36") (pin "43") (pinfunction "43_43") (pintype "passive"))
      (node (ref "U34") (pin "N24") (pinfunction "GPMC0_AD4_N24") (pintype "passive"))
    )
    (net (code "82") (name "/VOUT_D5_BOOTMODE5") (class "Default")
      (node (ref "J35") (pin "41") (pinfunction "41_41") (pintype "passive"))
      (node (ref "J36") (pin "41") (pinfunction "41_41") (pintype "passive"))
      (node (ref "U34") (pin "N27") (pinfunction "GPMC0_AD5_N27") (pintype "passive"))
    )
    (net (code "83") (name "/VOUT_D6_BOOTMODE6") (class "Default")
      (node (ref "J35") (pin "39") (pinfunction "39_39") (pintype "passive"))
      (node (ref "J36") (pin "39") (pinfunction "39_39") (pintype "passive"))
      (node (ref "U34") (pin "N28") (pinfunction "GPMC0_AD6_N28") (pintype "passive"))
    )
    (net (code "84") (name "/VOUT_D7_BOOTMODE7") (class "Default")
      (node (ref "J35") (pin "37") (pinfunction "37_37") (pintype "passive"))
      (node (ref "J36") (pin "37") (pinfunction "37_37") (pintype "passive"))
      (node (ref "U34") (pin "M25") (pinfunction "GPMC0_AD7_M25") (pintype "passive"))
    )
    (net (code "85") (name "/VOUT_D8_BOOTMODE8") (class "Default")
      (node (ref "J35") (pin "33") (pinfunction "33_33") (pintype "passive"))
      (node (ref "J36") (pin "33") (pinfunction "33_33") (pintype "passive"))
      (node (ref "U34") (pin "N23") (pinfunction "GPMC0_AD8_N23") (pintype "passive"))
    )
    (net (code "86") (name "/VOUT_D9_BOOTMODE9") (class "Default")
      (node (ref "J35") (pin "31") (pinfunction "31_31") (pintype "passive"))
      (node (ref "J36") (pin "31") (pinfunction "31_31") (pintype "passive"))
      (node (ref "U34") (pin "M26") (pinfunction "GPMC0_AD9_M26") (pintype "passive"))
    )
    (net (code "87") (name "/VOUT_D10_BOOTMODE10") (class "Default")
      (node (ref "J35") (pin "29") (pinfunction "29_29") (pintype "passive"))
      (node (ref "J36") (pin "29") (pinfunction "29_29") (pintype "passive"))
      (node (ref "U34") (pin "P28") (pinfunction "GPMC0_AD10_P28") (pintype "passive"))
    )
    (net (code "88") (name "/VOUT_D11_BOOTMODE11") (class "Default")
      (node (ref "J35") (pin "27") (pinfunction "27_27") (pintype "passive"))
      (node (ref "J36") (pin "27") (pinfunction "27_27") (pintype "passive"))
      (node (ref "U34") (pin "P27") (pinfunction "GPMC0_AD11_P27") (pintype "passive"))
    )
    (net (code "89") (name "/VOUT_D12_BOOTMODE12") (class "Default")
      (node (ref "J35") (pin "25") (pinfunction "25_25") (pintype "passive"))
      (node (ref "J36") (pin "25") (pinfunction "25_25") (pintype "passive"))
      (node (ref "U34") (pin "N26") (pinfunction "GPMC0_AD12_N26") (pintype "passive"))
    )
    (net (code "90") (name "/VOUT_D13_BOOTMODE13") (class "Default")
      (node (ref "J35") (pin "23") (pinfunction "23_23") (pintype "passive"))
      (node (ref "J36") (pin "23") (pinfunction "23_23") (pintype "passive"))
      (node (ref "U34") (pin "N25") (pinfunction "GPMC0_AD13_N25") (pintype "passive"))
    )
    (net (code "91") (name "/VOUT_D14_BOOTMODE14") (class "Default")
      (node (ref "J35") (pin "21") (pinfunction "21_21") (pintype "passive"))
      (node (ref "J36") (pin "21") (pinfunction "21_21") (pintype "passive"))
      (node (ref "U34") (pin "P24") (pinfunction "GPMC0_AD14_P24") (pintype "passive"))
    )
    (net (code "92") (name "/VOUT_D15_BOOTMODE15") (class "Default")
      (node (ref "J35") (pin "19") (pinfunction "19_19") (pintype "passive"))
      (node (ref "J36") (pin "19") (pinfunction "19_19") (pintype "passive"))
      (node (ref "U34") (pin "R27") (pinfunction "GPMC0_AD15_R27") (pintype "passive"))
    )
    (net (code "93") (name "/VOUT_D16") (class "Default")
      (node (ref "J35") (pin "15") (pinfunction "15_15") (pintype "passive"))
      (node (ref "J36") (pin "15") (pinfunction "15_15") (pintype "passive"))
      (node (ref "U34") (pin "R28") (pinfunction "GPMC0_CLK_R28") (pintype "passive"))
    )
    (net (code "94") (name "/VOUT_D17_BOOTMODE16") (class "Default")
      (node (ref "J35") (pin "13") (pinfunction "13_13") (pintype "passive"))
      (node (ref "J36") (pin "13") (pinfunction "13_13") (pintype "passive"))
      (node (ref "U34") (pin "P25") (pinfunction "GPMC0_ADVN_ALE_P25") (pintype "passive"))
    )
    (net (code "95") (name "/VOUT_D18_BOOTMODE17") (class "Default")
      (node (ref "J35") (pin "11") (pinfunction "11_11") (pintype "passive"))
      (node (ref "J36") (pin "11") (pinfunction "11_11") (pintype "passive"))
      (node (ref "U34") (pin "P26") (pinfunction "GPMC0_OEN_REN_P26") (pintype "passive"))
    )
    (net (code "96") (name "/VOUT_D19_BOOTMODE18") (class "Default")
      (node (ref "J35") (pin "9") (pinfunction "9_9") (pintype "passive"))
      (node (ref "J36") (pin "9") (pinfunction "9_9") (pintype "passive"))
      (node (ref "U34") (pin "U28") (pinfunction "GPMC0_WEN_U28") (pintype "passive"))
    )
    (net (code "97") (name "DGND") (class "Default")
      (node (ref "C245") (pin "1") (pinfunction "1_1") (pintype "passive"))
      (node (ref "C246") (pin "1") (pinfunction "1_1") (pintype "passive"))
      (node (ref "C247") (pin "1") (pinfunction "1_1") (pintype "passive"))
      (node (ref "C248") (pin "1") (pinfunction "1_1") (pintype "passive"))
      (node (ref "C619") (pin "2") (pinfunction "2_2") (pintype "passive"))
      (node (ref "C627") (pin "2") (pinfunction "2_2") (pintype "passive"))
      (node (ref "C628") (pin "2") (pinfunction "2_2") (pintype "passive"))
      (node (ref "C630") (pin "2") (pinfunction "2_2") (pintype "passive"))
      (node (ref "C638") (pin "2") (pinfunction "2_2") (pintype "passive"))
      (node (ref "C639") (pin "2") (pinfunction "2_2") (pintype "passive"))
      (node (ref "C640") (pin "2") (pinfunction "2_2") (pintype "passive"))
      (node (ref "C641") (pin "2") (pinfunction "2_2") (pintype "passive"))
      (node (ref "C656") (pin "2") (pinfunction "2_2") (pintype "passive"))
      (node (ref "C663") (pin "2") (pinfunction "2_2") (pintype "passive"))
      (node (ref "C664") (pin "2") (pinfunction "2_2") (pintype "passive"))
      (node (ref "C666") (pin "1") (pinfunction "1_1") (pintype "passive"))
      (node (ref "C670") (pin "1") (pinfunction "1_1") (pintype "passive"))
      (node (ref "C671") (pin "2") (pinfunction "2_2") (pintype "passive"))
      (node (ref "C675") (pin "1") (pinfunction "1_1") (pintype "passive"))
      (node (ref "C676") (pin "1") (pinfunction "1_1") (pintype "passive"))
      (node (ref "C677") (pin "2") (pinfunction "2_2") (pintype "passive"))
      (node (ref "J22") (pin "12") (pinfunction "12_12") (pintype "passive"))
      (node (ref "J22") (pin "16") (pinfunction "16_16") (pintype "passive"))
      (node (ref "J22") (pin "24") (pinfunction "24_24") (pintype "passive"))
      (node (ref "J22") (pin "41") (pinfunction "GND1_41") (pintype "passive"))
      (node (ref "J22") (pin "42") (pinfunction "GND2_42") (pintype "passive"))
      (node (ref "J22") (pin "43") (pinfunction "GND3_43") (pintype "passive"))
      (node (ref "J22") (pin "44") (pinfunction "GND4_44") (pintype "passive"))
      (node (ref "J35") (pin "12") (pinfunction "12_12") (pintype "passive"))
      (node (ref "J35") (pin "121") (pinfunction "121_121") (pintype "passive"))
      (node (ref "J35") (pin "122") (pinfunction "122_122") (pintype "passive"))
      (node (ref "J35") (pin "123") (pinfunction "123_123") (pintype "passive"))
      (node (ref "J35") (pin "124") (pinfunction "124_124") (pintype "passive"))
      (node (ref "J35") (pin "125") (pinfunction "125_125") (pintype "passive"))
      (node (ref "J35") (pin "126") (pinfunction "126_126") (pintype "passive"))
      (node (ref "J35") (pin "127") (pinfunction "127_127") (pintype "passive"))
      (node (ref "J35") (pin "128") (pinfunction "128_128") (pintype "passive"))
      (node (ref "J35") (pin "17") (pinfunction "17_17") (pintype "passive"))
      (node (ref "J35") (pin "22") (pinfunction "22_22") (pintype "passive"))
      (node (ref "J35") (pin "30") (pinfunction "30_30") (pintype "passive"))
      (node (ref "J35") (pin "35") (pinfunction "35_35") (pintype "passive"))
      (node (ref "J35") (pin "36") (pinfunction "36_36") (pintype "passive"))
      (node (ref "J36") (pin "12") (pinfunction "12_12") (pintype "passive"))
      (node (ref "J36") (pin "17") (pinfunction "17_17") (pintype "passive"))
      (node (ref "J36") (pin "22") (pinfunction "22_22") (pintype "passive"))
      (node (ref "J36") (pin "30") (pinfunction "30_30") (pintype "passive"))
      (node (ref "J36") (pin "35") (pinfunction "35_35") (pintype "passive"))
      (node (ref "J36") (pin "36") (pinfunction "36_36") (pintype "passive"))
      (node (ref "J36") (pin "61") (pinfunction "61_61") (pintype "passive"))
      (node (ref "J36") (pin "62") (pinfunction "62_62") (pintype "passive"))
      (node (ref "J36") (pin "63") (pinfunction "63_63") (pintype "passive"))
      (node (ref "J36") (pin "64") (pinfunction "64_64") (pintype "passive"))
      (node (ref "J39") (pin "10") (pinfunction "10_10") (pintype "passive"))
      (node (ref "J39") (pin "13") (pinfunction "13_13") (pintype "passive"))
      (node (ref "J39") (pin "16") (pinfunction "16_16") (pintype "passive"))
      (node (ref "J39") (pin "19") (pinfunction "19_19") (pintype "passive"))
      (node (ref "J39") (pin "22") (pinfunction "22_22") (pintype "passive"))
      (node (ref "J39") (pin "29") (pinfunction "29_29") (pintype "passive"))
      (node (ref "J39") (pin "33") (pinfunction "33_33") (pintype "passive"))
      (node (ref "J39") (pin "34") (pinfunction "34_34") (pintype "passive"))
      (node (ref "J39") (pin "6") (pinfunction "6_6") (pintype "passive"))
      (node (ref "J39") (pin "7") (pinfunction "7_7") (pintype "passive"))
      (node (ref "J39") (pin "SH1") (pinfunction "SH1_SH1") (pintype "passive"))
      (node (ref "J39") (pin "SH2") (pinfunction "SH2_SH2") (pintype "passive"))
      (node (ref "J39") (pin "SH3") (pinfunction "SH3_SH3") (pintype "passive"))
      (node (ref "J39") (pin "SH4") (pinfunction "SH4_SH4") (pintype "passive"))
      (node (ref "R676") (pin "1") (pinfunction "1_1") (pintype "passive"))
      (node (ref "R679") (pin "1") (pinfunction "1_1") (pintype "passive"))
      (node (ref "U100") (pin "11") (pinfunction "GND_11") (pintype "power_in"))
      (node (ref "U100") (pin "21") (pinfunction "PAD_21") (pintype "power_in"))
      (node (ref "U108") (pin "3") (pinfunction "GND_3") (pintype "power_in"))
      (node (ref "U111") (pin "11") (pinfunction "GND_11") (pintype "power_in"))
      (node (ref "U111") (pin "21") (pinfunction "PAD_21") (pintype "power_in"))
      (node (ref "U112") (pin "2") (pinfunction "GND_2") (pintype "power_in"))
      (node (ref "U114") (pin "2") (pinfunction "GND_2") (pintype "power_in"))
    )
    (net (code "98") (name "Net-(U100-OE)") (class "Default")
      (node (ref "R624") (pin "1") (pinfunction "1_1") (pintype "passive"))
      (node (ref "U100") (pin "10") (pinfunction "OE_10") (pintype "passive"))
    )
    (net (code "99") (name "Net-(U111-A8)") (class "Default")
      (node (ref "R676") (pin "2") (pinfunction "2_2") (pintype "passive"))
      (node (ref "U111") (pin "9") (pinfunction "A8_9") (pintype "bidirectional"))
    )
    (net (code "100") (name "Net-(U111-B8)") (class "Default")
      (node (ref "R679") (pin "2") (pinfunction "2_2") (pintype "passive"))
      (node (ref "U111") (pin "12") (pinfunction "B8_12") (pintype "bidirectional"))
    )
    (net (code "101") (name "Net-(U111-OE)") (class "Default")
      (node (ref "R688") (pin "1") (pinfunction "1_1") (pintype "passive"))
      (node (ref "U111") (pin "10") (pinfunction "OE_10") (pintype "passive"))
    )
    (net (code "102") (name "Net-(U112-ENABLE{slash}DISABLE)") (class "Default")
      (node (ref "R671") (pin "2") (pinfunction "2_2") (pintype "passive"))
      (node (ref "U112") (pin "1") (pinfunction "ENABLE/DISABLE_1") (pintype "bidirectional"))
    )
    (net (code "103") (name "Net-(U112-OUTPUT)") (class "Default")
      (node (ref "R674") (pin "1") (pinfunction "1_1") (pintype "passive"))
      (node (ref "U112") (pin "3") (pinfunction "OUTPUT_3") (pintype "output"))
    )
    (net (code "104") (name "Net-(U114-ENABLE{slash}DISABLE)") (class "Default")
      (node (ref "R700") (pin "2") (pinfunction "2_2") (pintype "passive"))
      (node (ref "U114") (pin "1") (pinfunction "ENABLE/DISABLE_1") (pintype "bidirectional"))
    )
    (net (code "105") (name "Net-(U114-OUTPUT)") (class "Default")
      (node (ref "R699") (pin "1") (pinfunction "1_1") (pintype "passive"))
      (node (ref "U114") (pin "3") (pinfunction "OUTPUT_3") (pintype "output"))
    )
    (net (code "106") (name "VCC1V8") (class "Default")
      (node (ref "C246") (pin "2") (pinfunction "2_2") (pintype "passive"))
      (node (ref "C248") (pin "2") (pinfunction "2_2") (pintype "passive"))
      (node (ref "C619") (pin "1") (pinfunction "1_1") (pintype "passive"))
      (node (ref "C639") (pin "1") (pinfunction "1_1") (pintype "passive"))
      (node (ref "C641") (pin "1") (pinfunction "1_1") (pintype "passive"))
      (node (ref "C675") (pin "2") (pinfunction "2_2") (pintype "passive"))
      (node (ref "C676") (pin "2") (pinfunction "2_2") (pintype "passive"))
      (node (ref "C677") (pin "1") (pinfunction "1_1") (pintype "passive"))
      (node (ref "J22") (pin "38") (pinfunction "38_38") (pintype "passive"))
      (node (ref "J22") (pin "40") (pinfunction "40_40") (pintype "passive"))
      (node (ref "J35") (pin "2") (pinfunction "2_2") (pintype "passive"))
      (node (ref "J35") (pin "4") (pinfunction "4_4") (pintype "passive"))
      (node (ref "J36") (pin "2") (pinfunction "2_2") (pintype "passive"))
      (node (ref "J36") (pin "4") (pinfunction "4_4") (pintype "passive"))
      (node (ref "J37") (pin "1") (pinfunction "1_1") (pintype "passive"))
      (node (ref "J39") (pin "4") (pinfunction "4_4") (pintype "passive"))
      (node (ref "J39") (pin "5") (pinfunction "5_5") (pintype "passive"))
      (node (ref "R624") (pin "2") (pinfunction "2_2") (pintype "passive"))
      (node (ref "R700") (pin "1") (pinfunction "1_1") (pintype "passive"))
      (node (ref "U100") (pin "2") (pinfunction "VCCA_2") (pintype "power_in"))
      (node (ref "U114") (pin "4") (pinfunction "VCC_4") (pintype "power_in"))
    )
    (net (code "107") (name "VCC3V3_IO") (class "Default")
      (node (ref "C245") (pin "2") (pinfunction "2_2") (pintype "passive"))
      (node (ref "C247") (pin "2") (pinfunction "2_2") (pintype "passive"))
      (node (ref "C627") (pin "1") (pinfunction "1_1") (pintype "passive"))
      (node (ref "C638") (pin "1") (pinfunction "1_1") (pintype "passive"))
      (node (ref "C640") (pin "1") (pinfunction "1_1") (pintype "passive"))
      (node (ref "C656") (pin "1") (pinfunction "1_1") (pintype "passive"))
      (node (ref "C664") (pin "1") (pinfunction "1_1") (pintype "passive"))
      (node (ref "C666") (pin "2") (pinfunction "2_2") (pintype "passive"))
      (node (ref "C670") (pin "2") (pinfunction "2_2") (pintype "passive"))
      (node (ref "C671") (pin "1") (pinfunction "1_1") (pintype "passive"))
      (node (ref "J22") (pin "30") (pinfunction "30_30") (pintype "passive"))
      (node (ref "J22") (pin "32") (pinfunction "32_32") (pintype "passive"))
      (node (ref "J22") (pin "34") (pinfunction "34_34") (pintype "passive"))
      (node (ref "J22") (pin "36") (pinfunction "36_36") (pintype "passive"))
      (node (ref "J35") (pin "56") (pinfunction "56_56") (pintype "passive"))
      (node (ref "J35") (pin "58") (pinfunction "58_58") (pintype "passive"))
      (node (ref "J35") (pin "60") (pinfunction "60_60") (pintype "passive"))
      (node (ref "J36") (pin "56") (pinfunction "56_56") (pintype "passive"))
      (node (ref "J36") (pin "58") (pinfunction "58_58") (pintype "passive"))
      (node (ref "J36") (pin "60") (pinfunction "60_60") (pintype "passive"))
      (node (ref "J37") (pin "3") (pinfunction "3_3") (pintype "passive"))
      (node (ref "J39") (pin "1") (pinfunction "1_1") (pintype "passive"))
      (node (ref "J39") (pin "2") (pinfunction "2_2") (pintype "passive"))
      (node (ref "J39") (pin "3") (pinfunction "3_3") (pintype "passive"))
      (node (ref "R658") (pin "2") (pinfunction "2_2") (pintype "passive"))
      (node (ref "R664") (pin "2") (pinfunction "2_2") (pintype "passive"))
      (node (ref "R671") (pin "1") (pinfunction "1_1") (pintype "passive"))
      (node (ref "U100") (pin "19") (pinfunction "VCCB_19") (pintype "power_in"))
      (node (ref "U108") (pin "5") (pinfunction "VCC_5") (pintype "power_in"))
      (node (ref "U111") (pin "19") (pinfunction "VCCB_19") (pintype "power_in"))
      (node (ref "U112") (pin "4") (pinfunction "VCC_4") (pintype "power_in"))
    )
    (net (code "108") (name "VCC_5V0") (class "Default")
      (node (ref "C628") (pin "1") (pinfunction "1_1") (pintype "passive"))
      (node (ref "C630") (pin "1") (pinfunction "1_1") (pintype "passive"))
      (node (ref "J35") (pin "55") (pinfunction "55_55") (pintype "passive"))
      (node (ref "J35") (pin "57") (pinfunction "57_57") (pintype "passive"))
      (node (ref "J35") (pin "59") (pinfunction "59_59") (pintype "passive"))
      (node (ref "J36") (pin "55") (pinfunction "55_55") (pintype "passive"))
      (node (ref "J36") (pin "57") (pinfunction "57_57") (pintype "passive"))
      (node (ref "J36") (pin "59") (pinfunction "59_59") (pintype "passive"))
    )
    (net (code "109") (name "VCC_HDR") (class "Default")
      (node (ref "C663") (pin "1") (pinfunction "1_1") (pintype "passive"))
      (node (ref "J37") (pin "2") (pinfunction "2_2") (pintype "passive"))
      (node (ref "R662") (pin "1") (pinfunction "1_1") (pintype "passive"))
      (node (ref "R666") (pin "1") (pinfunction "1_1") (pintype "passive"))
      (node (ref "R688") (pin "2") (pinfunction "2_2") (pintype "passive"))
      (node (ref "U111") (pin "2") (pinfunction "VCCA_2") (pintype "power_in"))
    )
    (net (code "110") (name "unconnected-(J22-Pad1)") (class "Default")
      (node (ref "J22") (pin "1") (pinfunction "1_1") (pintype "passive+no_connect"))
    )
    (net (code "111") (name "unconnected-(J22-Pad3)") (class "Default")
      (node (ref "J22") (pin "3") (pinfunction "3_3") (pintype "passive+no_connect"))
    )
    (net (code "112") (name "unconnected-(J22-Pad6)") (class "Default")
      (node (ref "J22") (pin "6") (pinfunction "6_6") (pintype "passive+no_connect"))
    )
    (net (code "113") (name "unconnected-(J22-Pad8)") (class "Default")
      (node (ref "J22") (pin "8") (pinfunction "8_8") (pintype "passive+no_connect"))
    )
    (net (code "114") (name "unconnected-(J22-Pad25)") (class "Default")
      (node (ref "J22") (pin "25") (pinfunction "25_25") (pintype "passive+no_connect"))
    )
    (net (code "115") (name "unconnected-(J22-Pad26)") (class "Default")
      (node (ref "J22") (pin "26") (pinfunction "26_26") (pintype "passive+no_connect"))
    )
    (net (code "116") (name "unconnected-(J22-Pad27)") (class "Default")
      (node (ref "J22") (pin "27") (pinfunction "27_27") (pintype "passive+no_connect"))
    )
    (net (code "117") (name "unconnected-(J22-Pad28)") (class "Default")
      (node (ref "J22") (pin "28") (pinfunction "28_28") (pintype "passive+no_connect"))
    )
    (net (code "118") (name "unconnected-(J22-Pad29)") (class "Default")
      (node (ref "J22") (pin "29") (pinfunction "29_29") (pintype "passive+no_connect"))
    )
    (net (code "119") (name "unconnected-(J22-Pad31)") (class "Default")
      (node (ref "J22") (pin "31") (pinfunction "31_31") (pintype "passive+no_connect"))
    )
    (net (code "120") (name "unconnected-(J22-Pad33)") (class "Default")
      (node (ref "J22") (pin "33") (pinfunction "33_33") (pintype "passive+no_connect"))
    )
    (net (code "121") (name "unconnected-(J22-Pad35)") (class "Default")
      (node (ref "J22") (pin "35") (pinfunction "35_35") (pintype "passive+no_connect"))
    )
    (net (code "122") (name "unconnected-(J22-Pad37)") (class "Default")
      (node (ref "J22") (pin "37") (pinfunction "37_37") (pintype "passive+no_connect"))
    )
    (net (code "123") (name "unconnected-(J22-Pad39)") (class "Default")
      (node (ref "J22") (pin "39") (pinfunction "39_39") (pintype "passive+no_connect"))
    )
    (net (code "124") (name "unconnected-(J35-Pad53)") (class "Default")
      (node (ref "J35") (pin "53") (pinfunction "53_53") (pintype "passive+no_connect"))
    )
    (net (code "125") (name "unconnected-(J35-Pad61)") (class "Default")
      (node (ref "J35") (pin "61") (pinfunction "61_61") (pintype "passive"))
    )
    (net (code "126") (name "unconnected-(J35-Pad62)") (class "Default")
      (node (ref "J35") (pin "62") (pinfunction "62_62") (pintype "passive"))
    )
    (net (code "127") (name "unconnected-(J35-Pad63)") (class "Default")
      (node (ref "J35") (pin "63") (pinfunction "63_63") (pintype "passive"))
    )
    (net (code "128") (name "unconnected-(J35-Pad64)") (class "Default")
      (node (ref "J35") (pin "64") (pinfunction "64_64") (pintype "passive"))
    )
    (net (code "129") (name "unconnected-(J35-Pad65)") (class "Default")
      (node (ref "J35") (pin "65") (pinfunction "65_65") (pintype "passive"))
    )
    (net (code "130") (name "unconnected-(J35-Pad66)") (class "Default")
      (node (ref "J35") (pin "66") (pinfunction "66_66") (pintype "passive"))
    )
    (net (code "131") (name "unconnected-(J35-Pad67)") (class "Default")
      (node (ref "J35") (pin "67") (pinfunction "67_67") (pintype "passive"))
    )
    (net (code "132") (name "unconnected-(J35-Pad68)") (class "Default")
      (node (ref "J35") (pin "68") (pinfunction "68_68") (pintype "passive"))
    )
    (net (code "133") (name "unconnected-(J35-Pad69)") (class "Default")
      (node (ref "J35") (pin "69") (pinfunction "69_69") (pintype "passive"))
    )
    (net (code "134") (name "unconnected-(J35-Pad70)") (class "Default")
      (node (ref "J35") (pin "70") (pinfunction "70_70") (pintype "passive"))
    )
    (net (code "135") (name "unconnected-(J35-Pad71)") (class "Default")
      (node (ref "J35") (pin "71") (pinfunction "71_71") (pintype "passive"))
    )
    (net (code "136") (name "unconnected-(J35-Pad72)") (class "Default")
      (node (ref "J35") (pin "72") (pinfunction "72_72") (pintype "passive"))
    )
    (net (code "137") (name "unconnected-(J35-Pad73)") (class "Default")
      (node (ref "J35") (pin "73") (pinfunction "73_73") (pintype "passive"))
    )
    (net (code "138") (name "unconnected-(J35-Pad74)") (class "Default")
      (node (ref "J35") (pin "74") (pinfunction "74_74") (pintype "passive"))
    )
    (net (code "139") (name "unconnected-(J35-Pad75)") (class "Default")
      (node (ref "J35") (pin "75") (pinfunction "75_75") (pintype "passive"))
    )
    (net (code "140") (name "unconnected-(J35-Pad76)") (class "Default")
      (node (ref "J35") (pin "76") (pinfunction "76_76") (pintype "passive"))
    )
    (net (code "141") (name "unconnected-(J35-Pad77)") (class "Default")
      (node (ref "J35") (pin "77") (pinfunction "77_77") (pintype "passive"))
    )
    (net (code "142") (name "unconnected-(J35-Pad78)") (class "Default")
      (node (ref "J35") (pin "78") (pinfunction "78_78") (pintype "passive"))
    )
    (net (code "143") (name "unconnected-(J35-Pad79)") (class "Default")
      (node (ref "J35") (pin "79") (pinfunction "79_79") (pintype "passive"))
    )
    (net (code "144") (name "unconnected-(J35-Pad80)") (class "Default")
      (node (ref "J35") (pin "80") (pinfunction "80_80") (pintype "passive"))
    )
    (net (code "145") (name "unconnected-(J35-Pad81)") (class "Default")
      (node (ref "J35") (pin "81") (pinfunction "81_81") (pintype "passive"))
    )
    (net (code "146") (name "unconnected-(J35-Pad82)") (class "Default")
      (node (ref "J35") (pin "82") (pinfunction "82_82") (pintype "passive"))
    )
    (net (code "147") (name "unconnected-(J35-Pad83)") (class "Default")
      (node (ref "J35") (pin "83") (pinfunction "83_83") (pintype "passive"))
    )
    (net (code "148") (name "unconnected-(J35-Pad84)") (class "Default")
      (node (ref "J35") (pin "84") (pinfunction "84_84") (pintype "passive"))
    )
    (net (code "149") (name "unconnected-(J35-Pad85)") (class "Default")
      (node (ref "J35") (pin "85") (pinfunction "85_85") (pintype "passive"))
    )
    (net (code "150") (name "unconnected-(J35-Pad86)") (class "Default")
      (node (ref "J35") (pin "86") (pinfunction "86_86") (pintype "passive"))
    )
    (net (code "151") (name "unconnected-(J35-Pad87)") (class "Default")
      (node (ref "J35") (pin "87") (pinfunction "87_87") (pintype "passive"))
    )
    (net (code "152") (name "unconnected-(J35-Pad88)") (class "Default")
      (node (ref "J35") (pin "88") (pinfunction "88_88") (pintype "passive"))
    )
    (net (code "153") (name "unconnected-(J35-Pad89)") (class "Default")
      (node (ref "J35") (pin "89") (pinfunction "89_89") (pintype "passive"))
    )
    (net (code "154") (name "unconnected-(J35-Pad90)") (class "Default")
      (node (ref "J35") (pin "90") (pinfunction "90_90") (pintype "passive"))
    )
    (net (code "155") (name "unconnected-(J35-Pad91)") (class "Default")
      (node (ref "J35") (pin "91") (pinfunction "91_91") (pintype "passive"))
    )
    (net (code "156") (name "unconnected-(J35-Pad92)") (class "Default")
      (node (ref "J35") (pin "92") (pinfunction "92_92") (pintype "passive"))
    )
    (net (code "157") (name "unconnected-(J35-Pad93)") (class "Default")
      (node (ref "J35") (pin "93") (pinfunction "93_93") (pintype "passive"))
    )
    (net (code "158") (name "unconnected-(J35-Pad94)") (class "Default")
      (node (ref "J35") (pin "94") (pinfunction "94_94") (pintype "passive"))
    )
    (net (code "159") (name "unconnected-(J35-Pad95)") (class "Default")
      (node (ref "J35") (pin "95") (pinfunction "95_95") (pintype "passive"))
    )
    (net (code "160") (name "unconnected-(J35-Pad96)") (class "Default")
      (node (ref "J35") (pin "96") (pinfunction "96_96") (pintype "passive"))
    )
    (net (code "161") (name "unconnected-(J35-Pad97)") (class "Default")
      (node (ref "J35") (pin "97") (pinfunction "97_97") (pintype "passive"))
    )
    (net (code "162") (name "unconnected-(J35-Pad98)") (class "Default")
      (node (ref "J35") (pin "98") (pinfunction "98_98") (pintype "passive"))
    )
    (net (code "163") (name "unconnected-(J35-Pad99)") (class "Default")
      (node (ref "J35") (pin "99") (pinfunction "99_99") (pintype "passive"))
    )
    (net (code "164") (name "unconnected-(J35-Pad100)") (class "Default")
      (node (ref "J35") (pin "100") (pinfunction "100_100") (pintype "passive"))
    )
    (net (code "165") (name "unconnected-(J35-Pad101)") (class "Default")
      (node (ref "J35") (pin "101") (pinfunction "101_101") (pintype "passive"))
    )
    (net (code "166") (name "unconnected-(J35-Pad102)") (class "Default")
      (node (ref "J35") (pin "102") (pinfunction "102_102") (pintype "passive"))
    )
    (net (code "167") (name "unconnected-(J35-Pad103)") (class "Default")
      (node (ref "J35") (pin "103") (pinfunction "103_103") (pintype "passive"))
    )
    (net (code "168") (name "unconnected-(J35-Pad104)") (class "Default")
      (node (ref "J35") (pin "104") (pinfunction "104_104") (pintype "passive"))
    )
    (net (code "169") (name "unconnected-(J35-Pad106)") (class "Default")
      (node (ref "J35") (pin "106") (pinfunction "106_106") (pintype "passive"))
    )
    (net (code "170") (name "unconnected-(J35-Pad108)") (class "Default")
      (node (ref "J35") (pin "108") (pinfunction "108_108") (pintype "passive"))
    )
    (net (code "171") (name "unconnected-(J35-Pad110)") (class "Default")
      (node (ref "J35") (pin "110") (pinfunction "110_110") (pintype "passive"))
    )
    (net (code "172") (name "unconnected-(J35-Pad112)") (class "Default")
      (node (ref "J35") (pin "112") (pinfunction "112_112") (pintype "passive"))
    )
    (net (code "173") (name "unconnected-(J35-Pad114)") (class "Default")
      (node (ref "J35") (pin "114") (pinfunction "114_114") (pintype "passive"))
    )
    (net (code "174") (name "unconnected-(J35-Pad116)") (class "Default")
      (node (ref "J35") (pin "116") (pinfunction "116_116") (pintype "passive"))
    )
    (net (code "175") (name "unconnected-(J35-Pad118)") (class "Default")
      (node (ref "J35") (pin "118") (pinfunction "118_118") (pintype "passive"))
    )
    (net (code "176") (name "unconnected-(J35-Pad120)") (class "Default")
      (node (ref "J35") (pin "120") (pinfunction "120_120") (pintype "passive"))
    )
    (net (code "177") (name "unconnected-(J36-Pad53)") (class "Default")
      (node (ref "J36") (pin "53") (pinfunction "53_53") (pintype "passive"))
    )
    (net (code "178") (name "unconnected-(J39-Pad27)") (class "Default")
      (node (ref "J39") (pin "27") (pinfunction "27_27") (pintype "passive+no_connect"))
    )
    (net (code "179") (name "unconnected-(J39-Pad28)") (class "Default")
      (node (ref "J39") (pin "28") (pinfunction "28_28") (pintype "passive+no_connect"))
    )
    (net (code "180") (name "unconnected-(J39-Pad35)") (class "Default")
      (node (ref "J39") (pin "35") (pinfunction "35_35") (pintype "passive+no_connect"))
    )
    (net (code "181") (name "unconnected-(J39-Pad36)") (class "Default")
      (node (ref "J39") (pin "36") (pinfunction "36_36") (pintype "passive+no_connect"))
    )
  )
)
